# Power_Circuit.net
KiCad netlist of a schematic drawn in Altium Designer
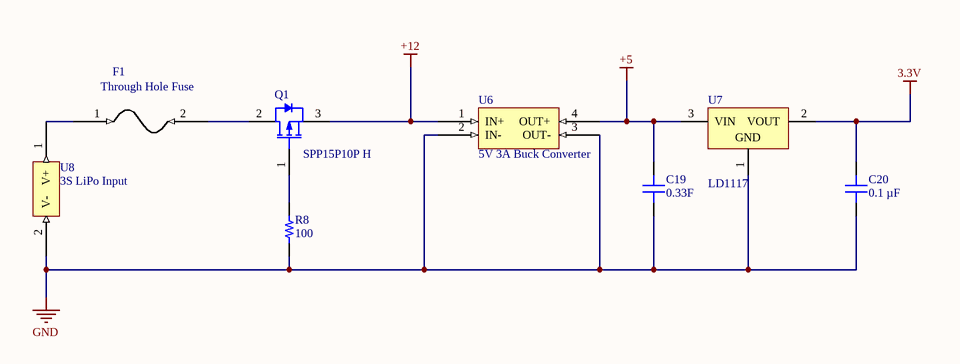
[diagram p0: Power_Circuit.SchDoc]

(export (version "E")
  (design (tool "Eeschema 10.0.6"))
  (components
    (comp (ref "C19")
      (value "0.33F")
      (footprint "CAP 1206_3216 - 0.8MM")
      (description "CAP CER 0.1UF 50V Y5V 1206")
      (fields (field (name "PART NUMBER") "CC1206ZRY5V9BB104") (field (name "MANUFACTURER") "Yageo"))
      (libsource (lib "Celestial Altium Library - altium_library") (part "Capacitor"))
    )
    (comp (ref "C20")
      (value "0.1 µF")
      (footprint "CAP 1206_3216 - 0.8MM")
      (description "CAP CER 0.1UF 50V Y5V 1206")
      (fields (field (name "PART NUMBER") "CC1206ZRY5V9BB104") (field (name "MANUFACTURER") "Yageo"))
      (libsource (lib "Celestial Altium Library - altium_library") (part "Capacitor"))
    )
    (comp (ref "F1")
      (value "Through Hole Fuse")
      (footprint "Through Hole Fuse-Footprint-1")
      (description "Fuse that be through the hole")
      (libsource (lib "") (part "New symbol 1_1"))
    )
    (comp (ref "Q1")
      (value "SPP15P10P H")
      (footprint "INF-PG-TO220-3-1_A_V")
      (fields (field (name "MANUFACTURER") "Infineon"))
      (libsource (lib "Altium Content Vault") (part "INF-PEMOS-GDS-3"))
    )
    (comp (ref "R8")
      (value "100")
      (footprint "RES 1206_3216")
      (description "RES SMD 10K OHM 1% 1/2W 1206")
      (fields (field (name "PART NUMBER") "ESR18EZPF1002") (field (name "MANUFACTURER") "Rohm Semiconductor"))
      (libsource (lib "Celestial Altium Library - altium_library") (part "Resistor"))
    )
    (comp (ref "U6")
      (value "5V 3A Buck Converter")
      (footprint "5V 3A Buck Converter-Footprint-1")
      (description "Adafruit RC Buck converter")
      (libsource (lib "Donados") (part "5V 3A Buck Converter-Symbol-1"))
    )
    (comp (ref "U7")
      (value "LD1117")
      (footprint "PCB - LEADED - TO - TO-220")
      (description "Linear Voltage Regulator IC  1 Output  1A TO-220AB")
      (fields (field (name "ROWAN PART NUMBER") "776") (field (name "MANUFACTURER") "STMicroelectronics"))
      (libsource (lib "RowanAltiumLibrary") (part "SCH - POWER - LINEAR VREG - LD1117"))
    )
    (comp (ref "U8")
      (value "3S LiPo Input")
      (footprint "3S LiPo Input-Footprint-2")
      (libsource (lib "Donados") (part "New symbol 1"))
    )
  )
  (nets
    (net (code "1") (name "+5") (class "Default")
      (node (ref "C19") (pin "2") (pinfunction "2_2") (pintype "passive"))
      (node (ref "U6") (pin "4") (pinfunction "OUT+_4") (pintype "input"))
      (node (ref "U7") (pin "3") (pinfunction "VIN_3") (pintype "power_in"))
    )
    (net (code "2") (name "+12") (class "Default")
      (node (ref "Q1") (pin "3") (pinfunction "SOURCE_3") (pintype "passive"))
      (node (ref "U6") (pin "1") (pinfunction "IN+_1") (pintype "input"))
    )
    (net (code "3") (name "3.3V") (class "Default")
      (node (ref "C20") (pin "2") (pinfunction "2_2") (pintype "passive"))
      (node (ref "U7") (pin "2") (pinfunction "VOUT_2") (pintype "power_in"))
    )
    (net (code "4") (name "GND") (class "Default")
      (node (ref "C19") (pin "1") (pinfunction "1_1") (pintype "passive"))
      (node (ref "C20") (pin "1") (pinfunction "1_1") (pintype "passive"))
      (node (ref "R8") (pin "1") (pinfunction "1_1") (pintype "passive"))
      (node (ref "U6") (pin "2") (pinfunction "IN-_2") (pintype "input"))
      (node (ref "U6") (pin "3") (pinfunction "OUT-_3") (pintype "input"))
      (node (ref "U7") (pin "1") (pinfunction "GND_1") (pintype "power_in"))
      (node (ref "U8") (pin "2") (pinfunction "V-_2") (pintype "input"))
    )
    (net (code "5") (name "Net-(Q1-DRAIN)") (class "Default")
      (node (ref "F1") (pin "2") (pintype "input"))
      (node (ref "Q1") (pin "2") (pinfunction "DRAIN_2") (pintype "passive"))
    )
    (net (code "6") (name "Net-(Q1-GATE)") (class "Default")
      (node (ref "Q1") (pin "1") (pinfunction "GATE_1") (pintype "passive"))
      (node (ref "R8") (pin "2") (pinfunction "2_2") (pintype "passive"))
    )
    (net (code "7") (name "Net-(U8-V+)") (class "Default")
      (node (ref "F1") (pin "1") (pintype "input"))
      (node (ref "U8") (pin "1") (pinfunction "V+_1") (pintype "output"))
    )
  )
)
